# Breadboard-Power-Adapter.net
KiCad netlist of a schematic drawn in EAGLE
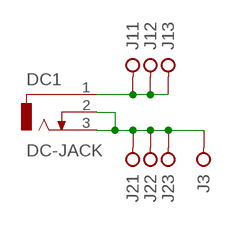
[diagram p0: schematic, sheet 1]

(export (version "E")
  (design (tool "Eeschema 10.0.6"))
  (components
    (comp (ref "DC1")
      (value "DC-JACK")
      (footprint "eagle-import:DC-JACK")
      (libsource (lib "eagle-import") (part "DC-JACK"))
    )
    (comp (ref "J1")
      (value "PINHD-1X3")
      (footprint "eagle-import:1X03")
      (libsource (lib "eagle-import") (part "PINHD-1X3"))
    )
    (comp (ref "J2")
      (value "PINHD-1X3")
      (footprint "eagle-import:1X03")
      (libsource (lib "eagle-import") (part "PINHD-1X3"))
    )
    (comp (ref "J3")
      (value "PINHD-1X1")
      (footprint "eagle-import:1X01")
      (libsource (lib "eagle-import") (part "PINHD-1X1"))
    )
  )
  (nets
    (net (code "1") (name "Net-(J1A-KL)") (class "Default")
      (node (ref "DC1") (pin "1") (pinfunction "1_1") (pintype "passive"))
      (node (ref "J1") (pin "1") (pinfunction "KL_1") (pintype "passive"))
      (node (ref "J1") (pin "2") (pinfunction "KL_2") (pintype "passive"))
      (node (ref "J1") (pin "3") (pinfunction "KL_3") (pintype "passive"))
    )
    (net (code "2") (name "Net-(J2A-KL)") (class "Default")
      (node (ref "DC1") (pin "2") (pinfunction "2_2") (pintype "passive"))
      (node (ref "DC1") (pin "3") (pinfunction "3_3") (pintype "passive"))
      (node (ref "J2") (pin "1") (pinfunction "KL_1") (pintype "passive"))
      (node (ref "J2") (pin "2") (pinfunction "KL_2") (pintype "passive"))
      (node (ref "J2") (pin "3") (pinfunction "KL_3") (pintype "passive"))
      (node (ref "J3") (pin "1") (pinfunction "KL_1") (pintype "passive"))
    )
  )
)
